# Receiver.net
KiCad netlist of a schematic drawn in Altium Designer
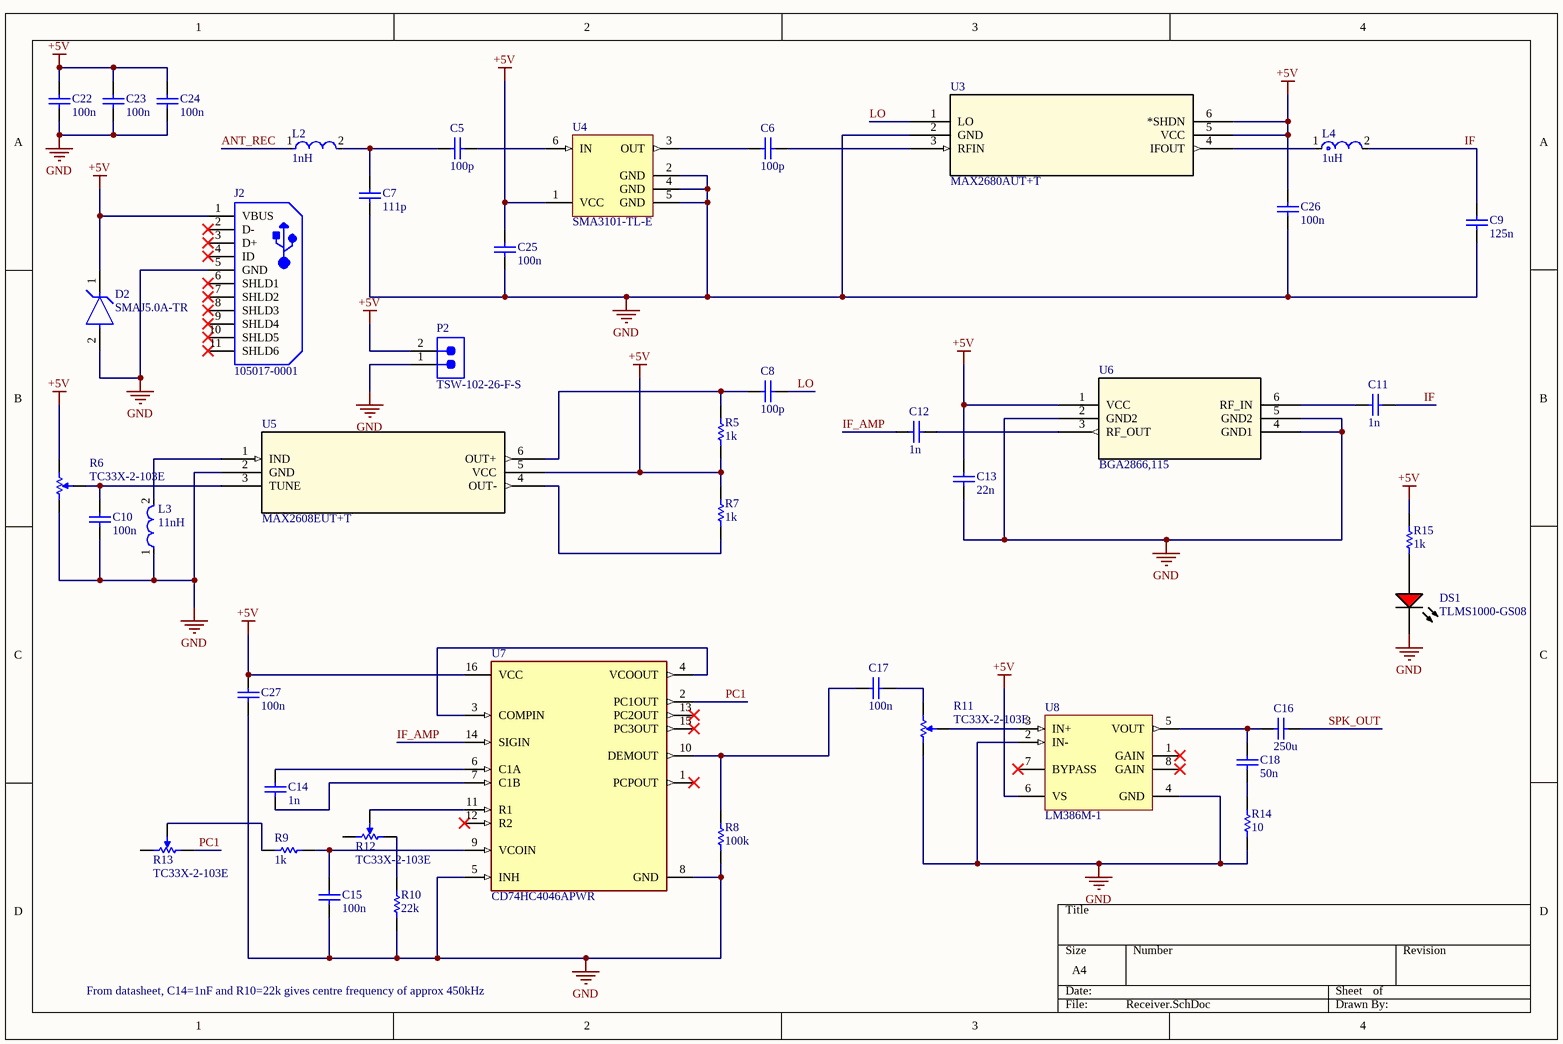
[diagram p0: Receiver.SchDoc]

(export (version "E")
  (design (tool "Eeschema 10.0.6"))
  (components
    (comp (ref "C5")
      (value "100p")
      (footprint "CAPC1608X90X35ML10T15")
      (description "Chip Capacitor, 0.1 uF, +/- 10%, 50 V, -55 to 125 degC, 0603 (1608 Metric), RoHS, Tape and Reel")
      (fields (field (name "TOLERANCE") "10%") (field (name "VOLTAGE") "50V"))
      (libsource (lib "Altium Content Vault") (part "CAP-NP-2"))
    )
    (comp (ref "C6")
      (value "100p")
      (footprint "CAPC1608X90X35ML10T15")
      (description "Chip Capacitor, 0.1 uF, +/- 10%, 50 V, -55 to 125 degC, 0603 (1608 Metric), RoHS, Tape and Reel")
      (fields (field (name "TOLERANCE") "10%") (field (name "VOLTAGE") "50V"))
      (libsource (lib "Altium Content Vault") (part "CAP-NP-2"))
    )
    (comp (ref "C7")
      (value "111p")
      (footprint "CAPC1608X90X35ML10T15")
      (description "Chip Capacitor, 0.1 uF, +/- 10%, 50 V, -55 to 125 degC, 0603 (1608 Metric), RoHS, Tape and Reel")
      (fields (field (name "TOLERANCE") "10%") (field (name "VOLTAGE") "50V"))
      (libsource (lib "Altium Content Vault") (part "CAP-NP-2"))
    )
    (comp (ref "C8")
      (value "100p")
      (footprint "CAPC1608X90X35ML10T15")
      (description "Chip Capacitor, 0.1 uF, +/- 10%, 50 V, -55 to 125 degC, 0603 (1608 Metric), RoHS, Tape and Reel")
      (fields (field (name "TOLERANCE") "10%") (field (name "VOLTAGE") "50V"))
      (libsource (lib "Altium Content Vault") (part "CAP-NP-2"))
    )
    (comp (ref "C9")
      (value "125n")
      (footprint "CAPC1608X90X35ML10T15")
      (description "Chip Capacitor, 0.1 uF, +/- 10%, 50 V, -55 to 125 degC, 0603 (1608 Metric), RoHS, Tape and Reel")
      (fields (field (name "TOLERANCE") "10%") (field (name "VOLTAGE") "50V"))
      (libsource (lib "Altium Content Vault") (part "CAP-NP-2"))
    )
    (comp (ref "C10")
      (value "100n")
      (footprint "CAPC1608X90X35ML10T15")
      (description "Chip Capacitor, 0.1 uF, +/- 10%, 50 V, -55 to 125 degC, 0603 (1608 Metric), RoHS, Tape and Reel")
      (fields (field (name "TOLERANCE") "10%") (field (name "VOLTAGE") "50V"))
      (libsource (lib "Altium Content Vault") (part "CAP-NP-2"))
    )
    (comp (ref "C11")
      (value "1n")
      (footprint "CAPC1608X90X35ML10T15")
      (description "Chip Capacitor, 0.1 uF, +/- 10%, 50 V, -55 to 125 degC, 0603 (1608 Metric), RoHS, Tape and Reel")
      (fields (field (name "TOLERANCE") "10%") (field (name "VOLTAGE") "50V"))
      (libsource (lib "Altium Content Vault") (part "CAP-NP-2"))
    )
    (comp (ref "C12")
      (value "1n")
      (footprint "CAPC1608X90X35ML10T15")
      (description "Chip Capacitor, 0.1 uF, +/- 10%, 50 V, -55 to 125 degC, 0603 (1608 Metric), RoHS, Tape and Reel")
      (fields (field (name "TOLERANCE") "10%") (field (name "VOLTAGE") "50V"))
      (libsource (lib "Altium Content Vault") (part "CAP-NP-2"))
    )
    (comp (ref "C13")
      (value "22n")
      (footprint "CAPC1608X90X35ML10T15")
      (description "Chip Capacitor, 0.1 uF, +/- 10%, 50 V, -55 to 125 degC, 0603 (1608 Metric), RoHS, Tape and Reel")
      (fields (field (name "TOLERANCE") "10%") (field (name "VOLTAGE") "50V"))
      (libsource (lib "Altium Content Vault") (part "CAP-NP-2"))
    )
    (comp (ref "C14")
      (value "1n")
      (footprint "CAPC1608X90X35ML10T15")
      (description "Chip Capacitor, 0.1 uF, +/- 10%, 50 V, -55 to 125 degC, 0603 (1608 Metric), RoHS, Tape and Reel")
      (fields (field (name "TOLERANCE") "10%") (field (name "VOLTAGE") "50V"))
      (libsource (lib "Altium Content Vault") (part "CAP-NP-2"))
    )
    (comp (ref "C15")
      (value "100n")
      (footprint "CAPC1608X90X35ML10T15")
      (description "Chip Capacitor, 0.1 uF, +/- 10%, 50 V, -55 to 125 degC, 0603 (1608 Metric), RoHS, Tape and Reel")
      (fields (field (name "TOLERANCE") "10%") (field (name "VOLTAGE") "50V"))
      (libsource (lib "Altium Content Vault") (part "CAP-NP-2"))
    )
    (comp (ref "C16")
      (value "250u")
      (footprint "CAPC1608X90X35ML10T15")
      (description "Chip Capacitor, 0.1 uF, +/- 10%, 50 V, -55 to 125 degC, 0603 (1608 Metric), RoHS, Tape and Reel")
      (fields (field (name "TOLERANCE") "10%") (field (name "VOLTAGE") "50V"))
      (libsource (lib "Altium Content Vault") (part "CAP-NP-2"))
    )
    (comp (ref "C17")
      (value "100n")
      (footprint "CAPC1608X90X35ML10T15")
      (description "Chip Capacitor, 0.1 uF, +/- 10%, 50 V, -55 to 125 degC, 0603 (1608 Metric), RoHS, Tape and Reel")
      (fields (field (name "TOLERANCE") "10%") (field (name "VOLTAGE") "50V"))
      (libsource (lib "Altium Content Vault") (part "CAP-NP-2"))
    )
    (comp (ref "C18")
      (value "50n")
      (footprint "CAPC1608X90X35ML10T15")
      (description "Chip Capacitor, 0.1 uF, +/- 10%, 50 V, -55 to 125 degC, 0603 (1608 Metric), RoHS, Tape and Reel")
      (fields (field (name "TOLERANCE") "10%") (field (name "VOLTAGE") "50V"))
      (libsource (lib "Altium Content Vault") (part "CAP-NP-2"))
    )
    (comp (ref "C22")
      (value "100n")
      (footprint "CAPC1608X90X35ML10T15")
      (description "Chip Capacitor, 0.1 uF, +/- 10%, 50 V, -55 to 125 degC, 0603 (1608 Metric), RoHS, Tape and Reel")
      (fields (field (name "TOLERANCE") "10%") (field (name "VOLTAGE") "50V"))
      (libsource (lib "Altium Content Vault") (part "CAP-NP-2"))
    )
    (comp (ref "C23")
      (value "100n")
      (footprint "CAPC1608X90X35ML10T15")
      (description "Chip Capacitor, 0.1 uF, +/- 10%, 50 V, -55 to 125 degC, 0603 (1608 Metric), RoHS, Tape and Reel")
      (fields (field (name "TOLERANCE") "10%") (field (name "VOLTAGE") "50V"))
      (libsource (lib "Altium Content Vault") (part "CAP-NP-2"))
    )
    (comp (ref "C24")
      (value "100n")
      (footprint "CAPC1608X90X35ML10T15")
      (description "Chip Capacitor, 0.1 uF, +/- 10%, 50 V, -55 to 125 degC, 0603 (1608 Metric), RoHS, Tape and Reel")
      (fields (field (name "TOLERANCE") "10%") (field (name "VOLTAGE") "50V"))
      (libsource (lib "Altium Content Vault") (part "CAP-NP-2"))
    )
    (comp (ref "C25")
      (value "100n")
      (footprint "CAPC1608X90X35ML10T15")
      (description "Chip Capacitor, 0.1 uF, +/- 10%, 50 V, -55 to 125 degC, 0603 (1608 Metric), RoHS, Tape and Reel")
      (fields (field (name "TOLERANCE") "10%") (field (name "VOLTAGE") "50V"))
      (libsource (lib "Altium Content Vault") (part "CAP-NP-2"))
    )
    (comp (ref "C26")
      (value "100n")
      (footprint "CAPC1608X90X35ML10T15")
      (description "Chip Capacitor, 0.1 uF, +/- 10%, 50 V, -55 to 125 degC, 0603 (1608 Metric), RoHS, Tape and Reel")
      (fields (field (name "TOLERANCE") "10%") (field (name "VOLTAGE") "50V"))
      (libsource (lib "Altium Content Vault") (part "CAP-NP-2"))
    )
    (comp (ref "C27")
      (value "100n")
      (footprint "CAPC1608X90X35ML10T15")
      (description "Chip Capacitor, 0.1 uF, +/- 10%, 50 V, -55 to 125 degC, 0603 (1608 Metric), RoHS, Tape and Reel")
      (fields (field (name "TOLERANCE") "10%") (field (name "VOLTAGE") "50V"))
      (libsource (lib "Altium Content Vault") (part "CAP-NP-2"))
    )
    (comp (ref "D2")
      (value "SMAJ5.0A-TR")
      (footprint "FP-SMA-MFG")
      (description "TVS DIODE 5V 13.4V SMA")
      (fields
        (field (name "MANUFACTURER") "STMicroelectronics")
        (field (name "OCTOPART") "https://octopart.com/smaj5.0a-tr-stmicroelectronics-347063")
      )
      (libsource (lib "Altium Content Vault") (part "7ddec9f632b8482e96f7745d0fbdf39"))
    )
    (comp (ref "DS1")
      (value "TLMS1000-GS08")
      (footprint "VISH-TLMS1000_V")
      (description "Low Current LED, 40 mW, 1.8 V, -40 to 100 degC, 2-Pin SMD (0603), RoHS, Tape and Reel")
      (fields (field (name "MANUFACTURER") "Vishay"))
      (libsource (lib "Altium Content Vault") (part "LED-RED-AK-2"))
    )
    (comp (ref "J2")
      (value "105017-0001")
      (footprint "USB-MICRO-B_V")
      (fields (field (name "MANUFACTURER") "Molex"))
      (libsource (lib "Altium Content Vault") (part "USB-5-6SHLD"))
    )
    (comp (ref "L2")
      (value "1nH")
      (footprint "FP-SRN2512-MFG")
      (description "FIXED IND 240NH 4.7A 24 MOHM SMD")
      (fields (field (name "TOLERANCE") "20%"))
      (libsource (lib "Altium Content Vault") (part "725321dda6339637d4d059423bc1c3c"))
    )
    (comp (ref "L3")
      (value "11nH")
      (footprint "FP-SRN2512-MFG")
      (description "FIXED IND 240NH 4.7A 24 MOHM SMD")
      (fields (field (name "TOLERANCE") "20%"))
      (libsource (lib "Altium Content Vault") (part "725321dda6339637d4d059423bc1c3c"))
    )
    (comp (ref "L4")
      (value "1uH")
      (footprint "FP-LQG18HH_00-IPC_A")
      (description "Multilayer type RF Inductor 2.2nH ±0.3nH 0.1Ω 1100mA 0603")
      (libsource (lib "Altium Content Vault") (part "4cc4b267dca4c8e51f7102f422741d8"))
    )
    (comp (ref "P2")
      (value "TSW-102-26-F-S")
      (footprint "SMTC-TSW-102-26-XX-S")
      (description "0.025\" SQ Post Header, Through-hole, Vertical, -55 to 125 degC, 2.54 mm Pitch, 2-Pin, Male, RoHS")
      (fields (field (name "MANUFACTURER") "Samtec"))
      (libsource (lib "Altium Content Vault") (part "SMTC-TSW-102-X-X-S-X"))
    )
    (comp (ref "R5")
      (value "1k")
      (footprint "RESC1608X55X25ML10T15")
      (description "Chip Resistor, 0 Ohm, +/- 5%, 0.1 W, -55 to 155 degC, 0603 (1608 Metric), RoHS, Tape and Reel")
      (fields (field (name "TOLERANCE") "5%") (field (name "MANUFACTURER") "Yageo"))
      (libsource (lib "Altium Content Vault") (part "RES-2"))
    )
    (comp (ref "R6")
      (value "TC33X-2-103E")
      (footprint "BOUR-TC33X-2_V")
      (description "Trimming Potentiometer, 10000 Ohm, -40 to 100 degC, 3-Pin SMD, RoHS, Tape and Reel")
      (fields (field (name "TOLERANCE") "25%") (field (name "MANUFACTURER") "Bourns"))
      (libsource (lib "Altium Content Vault") (part "RES-ADJ-3_A"))
    )
    (comp (ref "R7")
      (value "1k")
      (footprint "RESC1608X55X25ML10T15")
      (description "Chip Resistor, 0 Ohm, +/- 5%, 0.1 W, -55 to 155 degC, 0603 (1608 Metric), RoHS, Tape and Reel")
      (fields (field (name "TOLERANCE") "5%") (field (name "MANUFACTURER") "Yageo"))
      (libsource (lib "Altium Content Vault") (part "RES-2"))
    )
    (comp (ref "R8")
      (value "100k")
      (footprint "RESC1608X55X25ML10T15")
      (description "Chip Resistor, 0 Ohm, +/- 5%, 0.1 W, -55 to 155 degC, 0603 (1608 Metric), RoHS, Tape and Reel")
      (fields (field (name "TOLERANCE") "5%") (field (name "MANUFACTURER") "Yageo"))
      (libsource (lib "Altium Content Vault") (part "RES-2"))
    )
    (comp (ref "R9")
      (value "1k")
      (footprint "RESC1608X55X25ML10T15")
      (description "Chip Resistor, 0 Ohm, +/- 5%, 0.1 W, -55 to 155 degC, 0603 (1608 Metric), RoHS, Tape and Reel")
      (fields (field (name "TOLERANCE") "5%") (field (name "MANUFACTURER") "Yageo"))
      (libsource (lib "Altium Content Vault") (part "RES-2"))
    )
    (comp (ref "R10")
      (value "22k")
      (footprint "RESC1608X55X25ML10T15")
      (description "Chip Resistor, 0 Ohm, +/- 5%, 0.1 W, -55 to 155 degC, 0603 (1608 Metric), RoHS, Tape and Reel")
      (fields (field (name "TOLERANCE") "5%") (field (name "MANUFACTURER") "Yageo"))
      (libsource (lib "Altium Content Vault") (part "RES-2"))
    )
    (comp (ref "R11")
      (value "TC33X-2-103E")
      (footprint "BOUR-TC33X-2_V")
      (description "Trimming Potentiometer, 10000 Ohm, -40 to 100 degC, 3-Pin SMD, RoHS, Tape and Reel")
      (fields (field (name "TOLERANCE") "25%") (field (name "MANUFACTURER") "Bourns"))
      (libsource (lib "Altium Content Vault") (part "RES-ADJ-3_A"))
    )
    (comp (ref "R12")
      (value "TC33X-2-103E")
      (footprint "BOUR-TC33X-2_V")
      (description "Trimming Potentiometer, 10000 Ohm, -40 to 100 degC, 3-Pin SMD, RoHS, Tape and Reel")
      (fields (field (name "TOLERANCE") "25%") (field (name "MANUFACTURER") "Bourns"))
      (libsource (lib "Altium Content Vault") (part "RES-ADJ-3_A"))
    )
    (comp (ref "R13")
      (value "TC33X-2-103E")
      (footprint "BOUR-TC33X-2_V")
      (description "Trimming Potentiometer, 10000 Ohm, -40 to 100 degC, 3-Pin SMD, RoHS, Tape and Reel")
      (fields (field (name "TOLERANCE") "25%") (field (name "MANUFACTURER") "Bourns"))
      (libsource (lib "Altium Content Vault") (part "RES-ADJ-3_A"))
    )
    (comp (ref "R14")
      (value "10")
      (footprint "RESC1608X55X25ML10T15")
      (description "Chip Resistor, 0 Ohm, +/- 5%, 0.1 W, -55 to 155 degC, 0603 (1608 Metric), RoHS, Tape and Reel")
      (fields (field (name "TOLERANCE") "5%") (field (name "MANUFACTURER") "Yageo"))
      (libsource (lib "Altium Content Vault") (part "RES-2"))
    )
    (comp (ref "R15")
      (value "1k")
      (footprint "RESC1608X55X25ML10T15")
      (description "Chip Resistor, 0 Ohm, +/- 5%, 0.1 W, -55 to 155 degC, 0603 (1608 Metric), RoHS, Tape and Reel")
      (fields (field (name "TOLERANCE") "5%") (field (name "MANUFACTURER") "Yageo"))
      (libsource (lib "Altium Content Vault") (part "RES-2"))
    )
    (comp (ref "U3")
      (value "MAX2680AUT+T")
      (footprint "21-0058I_MXM")
      (description "No Description Available")
      (libsource (lib "Master") (part "MAX2680AUT+T"))
    )
    (comp (ref "U4")
      (value "SMA3101-TL-E")
      (footprint "ONSC-MCPH-6_V")
      (fields (field (name "MANUFACTURER") "On Semiconductor"))
      (libsource (lib "Altium Content Vault") (part "ONSC-SMA31XX-MCPH-6-419AS"))
    )
    (comp (ref "U5")
      (value "MAX2608EUT+T")
      (footprint "21-0058I_MXM")
      (description "No Description Available")
      (libsource (lib "Master") (part "MAX2608EUT+T"))
    )
    (comp (ref "U6")
      (value "BGA2866,115")
      (footprint "SOT_2815,115_NXP")
      (description "No Description Available")
      (libsource (lib "Master") (part "BGA2815,115"))
    )
    (comp (ref "U7")
      (value "CD74HC4046APWR")
      (footprint "FP-PW0016A-IPC_C")
      (description "IC PLL W/VCO 16-TSSOP")
      (libsource (lib "Altium Content Vault") (part "f78ae2031f710b6793e795eca8b3f2c"))
    )
    (comp (ref "U8")
      (value "LM386M-1")
      (footprint "D0008A_M")
      (description "Low Voltage Audio Power Amplifier, 8-pin Narrow SOIC")
      (fields (field (name "MANUFACTURER") "Texas Instruments"))
      (libsource (lib "Altium Content Vault") (part "AMP-APA-LM386-8"))
    )
  )
  (nets
    (net (code "1") (name "+5V") (class "Default")
      (node (ref "C13") (pin "2") (pinfunction "2_2") (pintype "passive"))
      (node (ref "C22") (pin "2") (pinfunction "2_2") (pintype "passive"))
      (node (ref "C23") (pin "2") (pinfunction "2_2") (pintype "passive"))
      (node (ref "C24") (pin "2") (pinfunction "2_2") (pintype "passive"))
      (node (ref "C25") (pin "2") (pinfunction "2_2") (pintype "passive"))
      (node (ref "C26") (pin "2") (pinfunction "2_2") (pintype "passive"))
      (node (ref "C27") (pin "2") (pinfunction "2_2") (pintype "passive"))
      (node (ref "D2") (pin "1") (pinfunction "K_1") (pintype "passive"))
      (node (ref "J2") (pin "1") (pinfunction "VBUS_1") (pintype "passive"))
      (node (ref "P2") (pin "2") (pinfunction "2_2") (pintype "passive"))
      (node (ref "R15") (pin "1") (pinfunction "1_1") (pintype "passive"))
      (node (ref "R5") (pin "1") (pinfunction "1_1") (pintype "passive"))
      (node (ref "R6") (pin "3") (pinfunction "3_3") (pintype "passive"))
      (node (ref "R7") (pin "2") (pinfunction "2_2") (pintype "passive"))
      (node (ref "U3") (pin "5") (pinfunction "VCC_5") (pintype "power_in"))
      (node (ref "U3") (pin "6") (pinfunction "*SHDN_6") (pintype "passive"))
      (node (ref "U4") (pin "1") (pinfunction "VCC_1") (pintype "power_in"))
      (node (ref "U5") (pin "5") (pinfunction "VCC_5") (pintype "power_in"))
      (node (ref "U6") (pin "1") (pinfunction "VCC_1") (pintype "power_in"))
      (node (ref "U7") (pin "16") (pinfunction "VCC_16") (pintype "power_in"))
      (node (ref "U8") (pin "6") (pinfunction "VS_6") (pintype "power_in"))
    )
    (net (code "2") (name "/ANT_REC") (class "Default")
      (node (ref "L2") (pin "1") (pinfunction "1_1") (pintype "passive"))
    )
    (net (code "3") (name "/IF") (class "Default")
      (node (ref "C11") (pin "2") (pinfunction "2_2") (pintype "passive"))
      (node (ref "C9") (pin "2") (pinfunction "2_2") (pintype "passive"))
      (node (ref "L4") (pin "2") (pinfunction "2_2") (pintype "passive"))
    )
    (net (code "4") (name "/IF_AMP") (class "Default")
      (node (ref "C12") (pin "1") (pinfunction "1_1") (pintype "passive"))
      (node (ref "U7") (pin "14") (pinfunction "SIGIN_14") (pintype "input"))
    )
    (net (code "5") (name "/LO") (class "Default")
      (node (ref "C8") (pin "2") (pinfunction "2_2") (pintype "passive"))
      (node (ref "U3") (pin "1") (pinfunction "LO_1") (pintype "passive"))
    )
    (net (code "6") (name "/PC1") (class "Default")
      (node (ref "R13") (pin "1") (pinfunction "1_1") (pintype "passive"))
      (node (ref "U7") (pin "2") (pinfunction "PC1OUT_2") (pintype "output"))
    )
    (net (code "7") (name "/SPK_OUT") (class "Default")
      (node (ref "C16") (pin "2") (pinfunction "2_2") (pintype "passive"))
    )
    (net (code "8") (name "GND") (class "Default")
      (node (ref "C10") (pin "1") (pinfunction "1_1") (pintype "passive"))
      (node (ref "C13") (pin "1") (pinfunction "1_1") (pintype "passive"))
      (node (ref "C15") (pin "1") (pinfunction "1_1") (pintype "passive"))
      (node (ref "C22") (pin "1") (pinfunction "1_1") (pintype "passive"))
      (node (ref "C23") (pin "1") (pinfunction "1_1") (pintype "passive"))
      (node (ref "C24") (pin "1") (pinfunction "1_1") (pintype "passive"))
      (node (ref "C25") (pin "1") (pinfunction "1_1") (pintype "passive"))
      (node (ref "C26") (pin "1") (pinfunction "1_1") (pintype "passive"))
      (node (ref "C27") (pin "1") (pinfunction "1_1") (pintype "passive"))
      (node (ref "C7") (pin "1") (pinfunction "1_1") (pintype "passive"))
      (node (ref "C9") (pin "1") (pinfunction "1_1") (pintype "passive"))
      (node (ref "D2") (pin "2") (pinfunction "A_2") (pintype "passive"))
      (node (ref "DS1") (pin "2") (pinfunction "K_2") (pintype "passive"))
      (node (ref "J2") (pin "5") (pinfunction "GND_5") (pintype "passive"))
      (node (ref "L3") (pin "1") (pinfunction "1_1") (pintype "passive"))
      (node (ref "P2") (pin "1") (pinfunction "1_1") (pintype "passive"))
      (node (ref "R10") (pin "2") (pinfunction "2_2") (pintype "passive"))
      (node (ref "R11") (pin "1") (pinfunction "1_1") (pintype "passive"))
      (node (ref "R14") (pin "2") (pinfunction "2_2") (pintype "passive"))
      (node (ref "R6") (pin "1") (pinfunction "1_1") (pintype "passive"))
      (node (ref "R8") (pin "2") (pinfunction "2_2") (pintype "passive"))
      (node (ref "U3") (pin "2") (pinfunction "GND_2") (pintype "power_in"))
      (node (ref "U4") (pin "2") (pinfunction "GND_2") (pintype "power_in"))
      (node (ref "U4") (pin "4") (pinfunction "GND_4") (pintype "power_in"))
      (node (ref "U4") (pin "5") (pinfunction "GND_5") (pintype "power_in"))
      (node (ref "U5") (pin "2") (pinfunction "GND_2") (pintype "power_in"))
      (node (ref "U6") (pin "2") (pinfunction "GND2_2") (pintype "power_in"))
      (node (ref "U6") (pin "4") (pinfunction "GND1_4") (pintype "power_in"))
      (node (ref "U6") (pin "5") (pinfunction "GND2_5") (pintype "power_in"))
      (node (ref "U7") (pin "5") (pinfunction "INH_5") (pintype "input"))
      (node (ref "U7") (pin "8") (pinfunction "GND_8") (pintype "power_in"))
      (node (ref "U8") (pin "2") (pinfunction "IN-_2") (pintype "input"))
      (node (ref "U8") (pin "4") (pinfunction "GND_4") (pintype "power_in"))
    )
    (net (code "9") (name "Net-(C5-Pad1)") (class "Default")
      (node (ref "C5") (pin "1") (pinfunction "1_1") (pintype "passive"))
      (node (ref "C7") (pin "2") (pinfunction "2_2") (pintype "passive"))
      (node (ref "L2") (pin "2") (pinfunction "2_2") (pintype "passive"))
    )
    (net (code "10") (name "Net-(C17-Pad2)") (class "Default")
      (node (ref "C17") (pin "2") (pinfunction "2_2") (pintype "passive"))
      (node (ref "R11") (pin "3") (pinfunction "3_3") (pintype "passive"))
    )
    (net (code "11") (name "Net-(C18-Pad1)") (class "Default")
      (node (ref "C18") (pin "1") (pinfunction "1_1") (pintype "passive"))
      (node (ref "R14") (pin "1") (pinfunction "1_1") (pintype "passive"))
    )
    (net (code "12") (name "Net-(DS1-A)") (class "Default")
      (node (ref "DS1") (pin "1") (pinfunction "A_1") (pintype "passive"))
      (node (ref "R15") (pin "2") (pinfunction "2_2") (pintype "passive"))
    )
    (net (code "13") (name "Net-(R10-Pad1)") (class "Default")
      (node (ref "R10") (pin "1") (pinfunction "1_1") (pintype "passive"))
      (node (ref "R12") (pin "1") (pinfunction "1_1") (pintype "passive"))
    )
    (net (code "14") (name "Net-(R13-Pad2)") (class "Default")
      (node (ref "R13") (pin "2") (pinfunction "2_2") (pintype "passive"))
      (node (ref "R9") (pin "2") (pinfunction "2_2") (pintype "passive"))
    )
    (net (code "15") (name "Net-(U3-IFOUT)") (class "Default")
      (node (ref "L4") (pin "1") (pinfunction "1_1") (pintype "passive"))
      (node (ref "U3") (pin "4") (pinfunction "IFOUT_4") (pintype "output"))
    )
    (net (code "16") (name "Net-(U3-RFIN)") (class "Default")
      (node (ref "C6") (pin "2") (pinfunction "2_2") (pintype "passive"))
      (node (ref "U3") (pin "3") (pinfunction "RFIN_3") (pintype "input"))
    )
    (net (code "17") (name "Net-(U4-IN)") (class "Default")
      (node (ref "C5") (pin "2") (pinfunction "2_2") (pintype "passive"))
      (node (ref "U4") (pin "6") (pinfunction "IN_6") (pintype "input"))
    )
    (net (code "18") (name "Net-(U4-OUT)") (class "Default")
      (node (ref "C6") (pin "1") (pinfunction "1_1") (pintype "passive"))
      (node (ref "U4") (pin "3") (pinfunction "OUT_3") (pintype "output"))
    )
    (net (code "19") (name "Net-(U5-IND)") (class "Default")
      (node (ref "L3") (pin "2") (pinfunction "2_2") (pintype "passive"))
      (node (ref "U5") (pin "1") (pinfunction "IND_1") (pintype "input"))
    )
    (net (code "20") (name "Net-(U5-OUT+)") (class "Default")
      (node (ref "C8") (pin "1") (pinfunction "1_1") (pintype "passive"))
      (node (ref "R5") (pin "2") (pinfunction "2_2") (pintype "passive"))
      (node (ref "U5") (pin "6") (pinfunction "OUT+_6") (pintype "output"))
    )
    (net (code "21") (name "Net-(U5-OUT-)") (class "Default")
      (node (ref "R7") (pin "1") (pinfunction "1_1") (pintype "passive"))
      (node (ref "U5") (pin "4") (pinfunction "OUT-_4") (pintype "output"))
    )
    (net (code "22") (name "Net-(U5-TUNE)") (class "Default")
      (node (ref "C10") (pin "2") (pinfunction "2_2") (pintype "passive"))
      (node (ref "R6") (pin "2") (pinfunction "2_2") (pintype "passive"))
      (node (ref "U5") (pin "3") (pinfunction "TUNE_3") (pintype "passive"))
    )
    (net (code "23") (name "Net-(U6-RF_IN)") (class "Default")
      (node (ref "C11") (pin "1") (pinfunction "1_1") (pintype "passive"))
      (node (ref "U6") (pin "6") (pinfunction "RF_IN_6") (pintype "passive"))
    )
    (net (code "24") (name "Net-(U6-RF_OUT)") (class "Default")
      (node (ref "C12") (pin "2") (pinfunction "2_2") (pintype "passive"))
      (node (ref "U6") (pin "3") (pinfunction "RF_OUT_3") (pintype "output"))
    )
    (net (code "25") (name "Net-(U7-C1A)") (class "Default")
      (node (ref "C14") (pin "2") (pinfunction "2_2") (pintype "passive"))
      (node (ref "U7") (pin "6") (pinfunction "C1A_6") (pintype "input"))
    )
    (net (code "26") (name "Net-(U7-C1B)") (class "Default")
      (node (ref "C14") (pin "1") (pinfunction "1_1") (pintype "passive"))
      (node (ref "U7") (pin "7") (pinfunction "C1B_7") (pintype "input"))
    )
    (net (code "27") (name "Net-(U7-COMPIN)") (class "Default")
      (node (ref "U7") (pin "3") (pinfunction "COMPIN_3") (pintype "input"))
      (node (ref "U7") (pin "4") (pinfunction "VCOOUT_4") (pintype "output"))
    )
    (net (code "28") (name "Net-(U7-DEMOUT)") (class "Default")
      (node (ref "C17") (pin "1") (pinfunction "1_1") (pintype "passive"))
      (node (ref "R8") (pin "1") (pinfunction "1_1") (pintype "passive"))
      (node (ref "U7") (pin "10") (pinfunction "DEMOUT_10") (pintype "output"))
    )
    (net (code "29") (name "Net-(U7-R1)") (class "Default")
      (node (ref "R12") (pin "2") (pinfunction "2_2") (pintype "passive"))
      (node (ref "U7") (pin "11") (pinfunction "R1_11") (pintype "input"))
    )
    (net (code "30") (name "Net-(U7-VCOIN)") (class "Default")
      (node (ref "C15") (pin "2") (pinfunction "2_2") (pintype "passive"))
      (node (ref "R9") (pin "1") (pinfunction "1_1") (pintype "passive"))
      (node (ref "U7") (pin "9") (pinfunction "VCOIN_9") (pintype "input"))
    )
    (net (code "31") (name "Net-(U8-IN+)") (class "Default")
      (node (ref "R11") (pin "2") (pinfunction "2_2") (pintype "passive"))
      (node (ref "U8") (pin "3") (pinfunction "IN+_3") (pintype "input"))
    )
    (net (code "32") (name "Net-(U8-VOUT)") (class "Default")
      (node (ref "C16") (pin "1") (pinfunction "1_1") (pintype "passive"))
      (node (ref "C18") (pin "2") (pinfunction "2_2") (pintype "passive"))
      (node (ref "U8") (pin "5") (pinfunction "VOUT_5") (pintype "output"))
    )
    (net (code "33") (name "unconnected-(J2-D+-Pad3)") (class "Default")
      (node (ref "J2") (pin "3") (pinfunction "D+_3") (pintype "passive+no_connect"))
    )
    (net (code "34") (name "unconnected-(J2-D--Pad2)") (class "Default")
      (node (ref "J2") (pin "2") (pinfunction "D-_2") (pintype "passive+no_connect"))
    )
    (net (code "35") (name "unconnected-(J2-ID-Pad4)") (class "Default")
      (node (ref "J2") (pin "4") (pinfunction "ID_4") (pintype "passive+no_connect"))
    )
    (net (code "36") (name "unconnected-(J2-SHLD1-Pad6)") (class "Default")
      (node (ref "J2") (pin "6") (pinfunction "SHLD1_6") (pintype "passive+no_connect"))
    )
    (net (code "37") (name "unconnected-(J2-SHLD2-Pad7)") (class "Default")
      (node (ref "J2") (pin "7") (pinfunction "SHLD2_7") (pintype "passive+no_connect"))
    )
    (net (code "38") (name "unconnected-(J2-SHLD3-Pad8)") (class "Default")
      (node (ref "J2") (pin "8") (pinfunction "SHLD3_8") (pintype "passive+no_connect"))
    )
    (net (code "39") (name "unconnected-(J2-SHLD4-Pad9)") (class "Default")
      (node (ref "J2") (pin "9") (pinfunction "SHLD4_9") (pintype "passive+no_connect"))
    )
    (net (code "40") (name "unconnected-(J2-SHLD5-Pad10)") (class "Default")
      (node (ref "J2") (pin "10") (pinfunction "SHLD5_10") (pintype "passive+no_connect"))
    )
    (net (code "41") (name "unconnected-(J2-SHLD6-Pad11)") (class "Default")
      (node (ref "J2") (pin "11") (pinfunction "SHLD6_11") (pintype "passive+no_connect"))
    )
    (net (code "42") (name "unconnected-(R12-Pad3)") (class "Default")
      (node (ref "R12") (pin "3") (pinfunction "3_3") (pintype "passive"))
    )
    (net (code "43") (name "unconnected-(R13-Pad3)") (class "Default")
      (node (ref "R13") (pin "3") (pinfunction "3_3") (pintype "passive"))
    )
    (net (code "44") (name "unconnected-(U7-PC2OUT-Pad13)") (class "Default")
      (node (ref "U7") (pin "13") (pinfunction "PC2OUT_13") (pintype "output+no_connect"))
    )
    (net (code "45") (name "unconnected-(U7-PC3OUT-Pad15)") (class "Default")
      (node (ref "U7") (pin "15") (pinfunction "PC3OUT_15") (pintype "output+no_connect"))
    )
    (net (code "46") (name "unconnected-(U7-PCPOUT-Pad1)") (class "Default")
      (node (ref "U7") (pin "1") (pinfunction "PCPOUT_1") (pintype "output+no_connect"))
    )
    (net (code "47") (name "unconnected-(U7-R2-Pad12)") (class "Default")
      (node (ref "U7") (pin "12") (pinfunction "R2_12") (pintype "input+no_connect"))
    )
    (net (code "48") (name "unconnected-(U8-BYPASS-Pad7)") (class "Default")
      (node (ref "U8") (pin "7") (pinfunction "BYPASS_7") (pintype "passive+no_connect"))
    )
    (net (code "49") (name "unconnected-(U8-GAIN-Pad1)") (class "Default")
      (node (ref "U8") (pin "1") (pinfunction "GAIN_1") (pintype "passive+no_connect"))
    )
    (net (code "50") (name "unconnected-(U8-GAIN-Pad8)") (class "Default")
      (node (ref "U8") (pin "8") (pinfunction "GAIN_8") (pintype "passive+no_connect"))
    )
  )
)
